# FPGA_Altera_Cyclone_III_Starter_Kit.net
KiCad netlist of a schematic drawn in Altium Designer
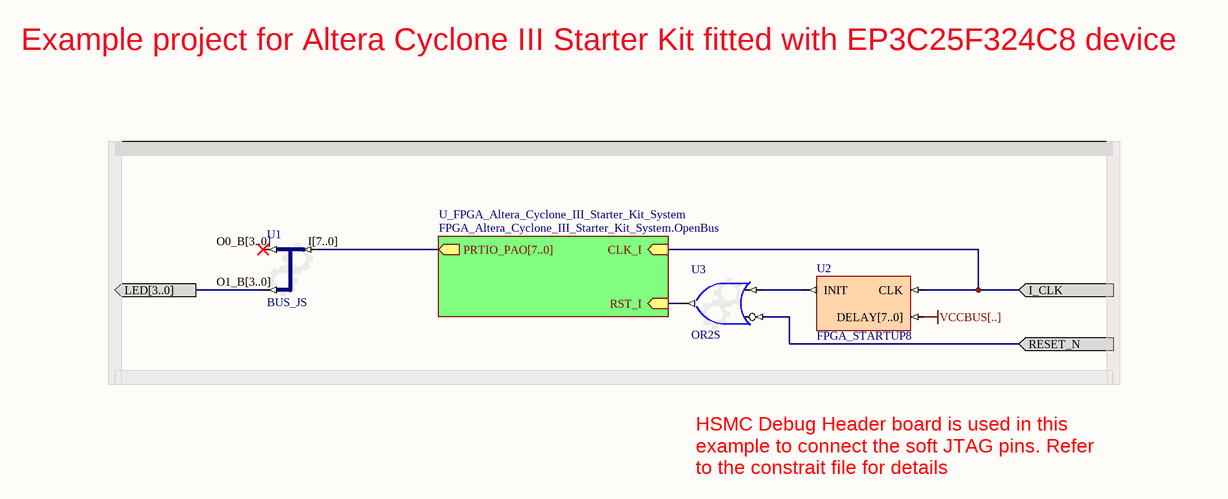
[diagram p0: FPGA_Altera_Cyclone_III_Starter_Kit.SchDoc]

(export (version "E")
  (design (tool "Eeschema 10.0.6"))
  (components
    (comp (ref "U1")
      (value "BUS_JS")
      (description "Configurable Bus Joiner/Splitter")
      (fields (field (name "PUBLISHER") "Altium Limited"))
      (libsource (lib "FPGA Configurable Generic") (part "BUS_JS"))
    )
    (comp (ref "U2")
      (value "FPGA_STARTUP8")
      (description "FPGA Startup With 8 Bit Delay")
      (fields (field (name "PUBLISHER") "Altium Limited"))
      (libsource (lib "FPGA Peripherals") (part "FPGA_STARTUP8"))
    )
    (comp (ref "U3")
      (value "OR2S")
      (description "Configurable Generic Gate")
      (fields (field (name "PUBLISHER") "Altium Limited"))
      (libsource (lib "FPGA Configurable Generic") (part "GATE"))
    )
  )
  (nets
    (net (code "5") (name "/I_CLK") (class "Default")
      (node (ref "U2") (pin "CLK") (pinfunction "CLK_CLK") (pintype "input"))
    )
    (net (code "6") (name "/LED[3..0]") (class "Default")
      (node (ref "U1") (pin "O1_B[3..0]") (pinfunction "O1_B[3..0]_O1_B[3..0]") (pintype "output"))
    )
    (net (code "7") (name "/PRTIO_PAO[7..0]") (class "Default")
      (node (ref "U1") (pin "I[7..0]") (pinfunction "I[7..0]_I[7..0]") (pintype "input"))
    )
    (net (code "8") (name "/RESET_N") (class "Default")
      (node (ref "U3") (pin "I1") (pinfunction "I1_I1") (pintype "input"))
    )
    (net (code "9") (name "/RST_I") (class "Default")
      (node (ref "U3") (pin "O") (pinfunction "O_O") (pintype "output"))
    )
    (net (code "10") (name "Net-(U2-PadINIT)") (class "Default")
      (node (ref "U2") (pin "INIT") (pinfunction "INIT_INIT") (pintype "output"))
      (node (ref "U3") (pin "I0") (pinfunction "I0_I0") (pintype "input"))
    )
    (net (code "11") (name "VCCBUS[..]") (class "Default")
      (node (ref "U2") (pin "DELAY[7..0]") (pinfunction "DELAY[7..0]_DELAY[7..0]") (pintype "input"))
    )
    (net (code "12") (name "unconnected-(U1-PadO0_B[3..0])") (class "Default")
      (node (ref "U1") (pin "O0_B[3..0]") (pinfunction "O0_B[3..0]_O0_B[3..0]") (pintype "output+no_connect"))
    )
  )
)
